# Shield_Grove_I2C.net
KiCad netlist of a schematic drawn in EAGLE
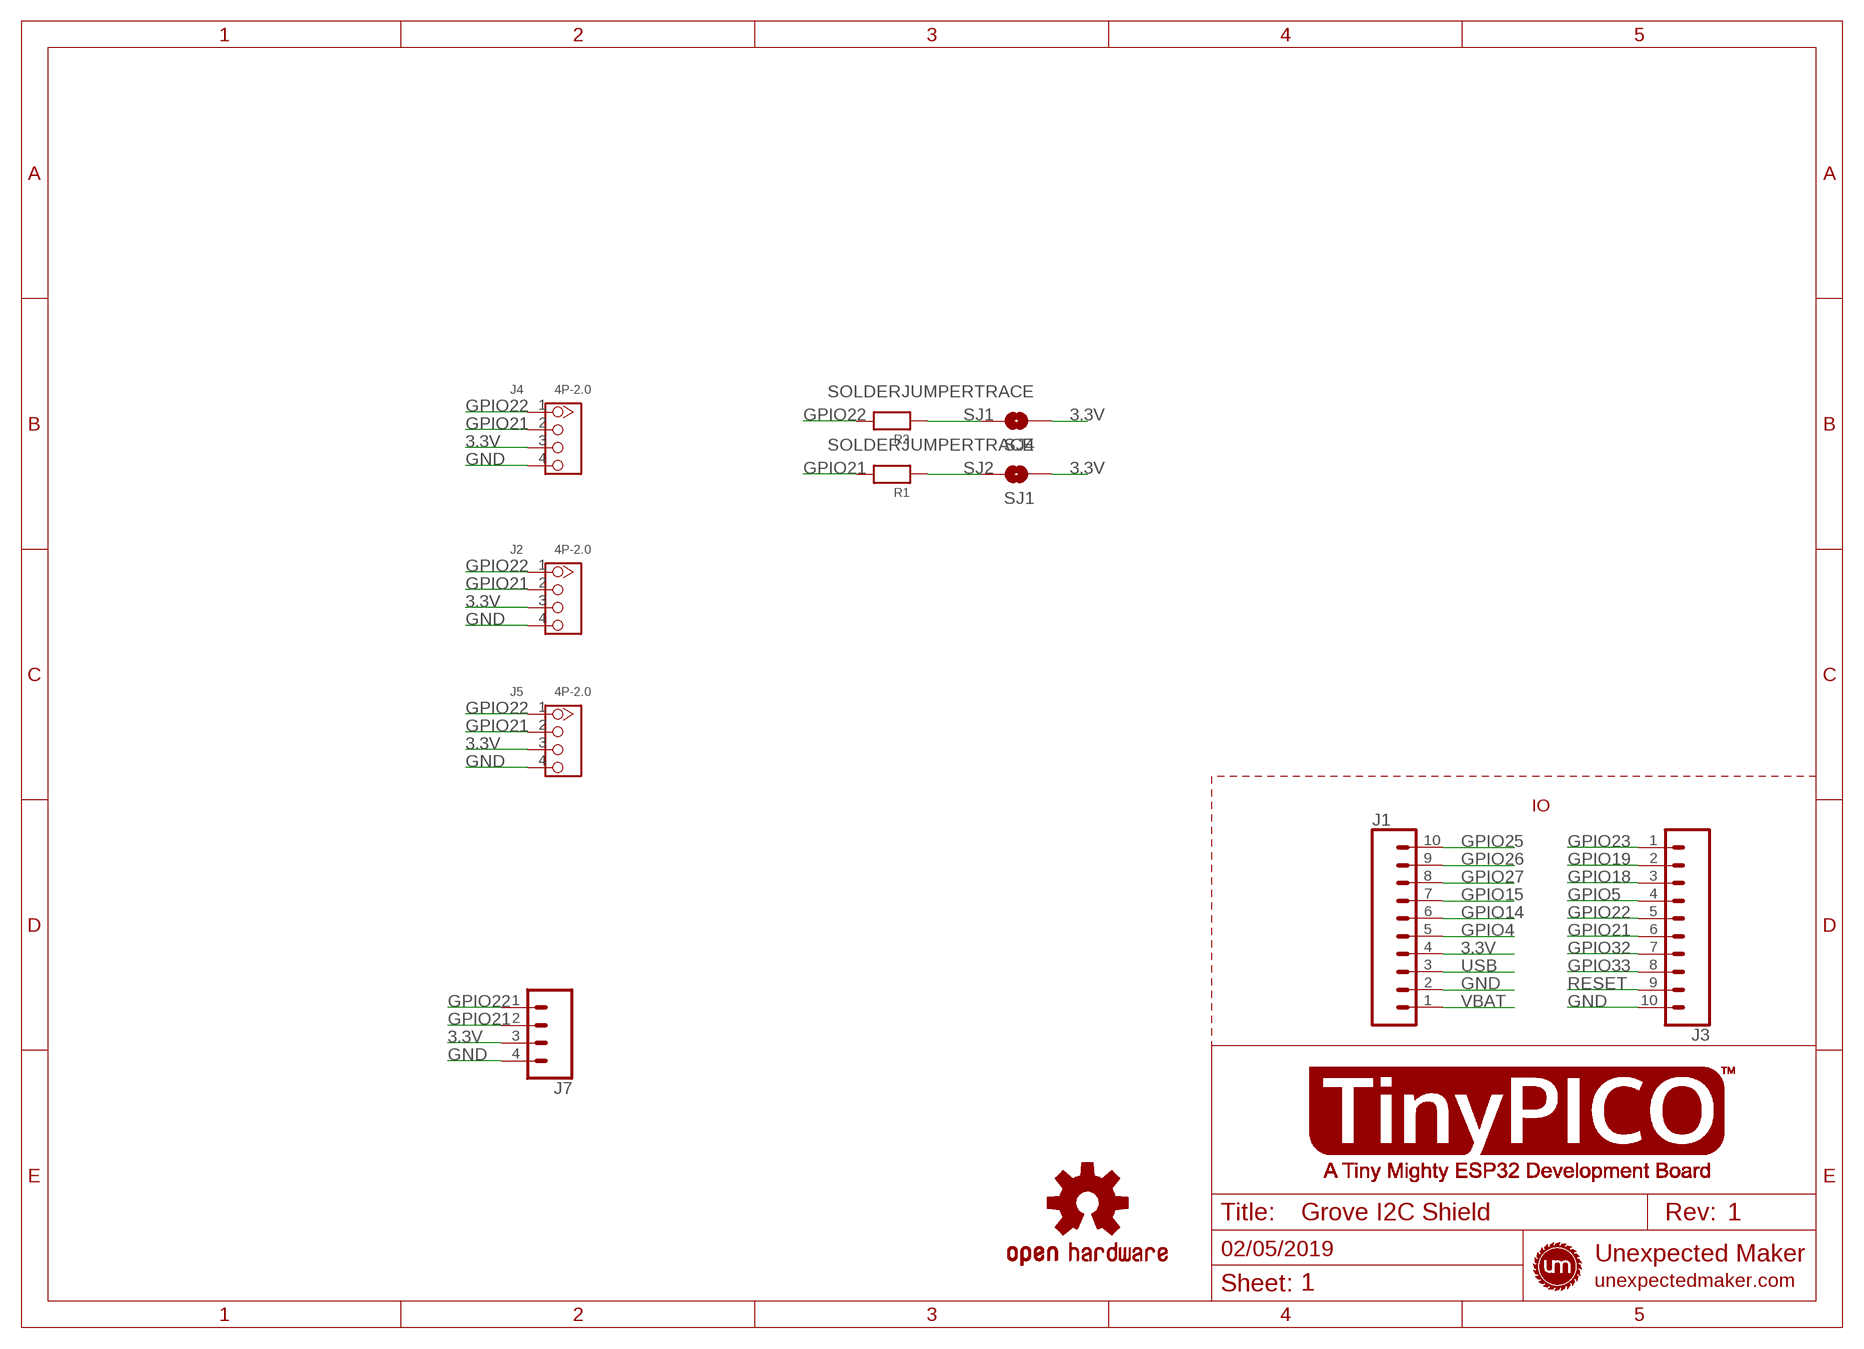
[diagram p0: schematic, sheet 1]

(export (version "E")
  (design (tool "Eeschema 10.0.6"))
  (components
    (comp (ref "J1")
      (value "TINYPICO_HEADER_10NO_SILK_PTH_FEMALE")
      (footprint "eagle-import:1X10_NO_SILK")
      (libsource (lib "eagle-import") (part "TINYPICO_HEADER_10NO_SILK_PTH_FEMALE"))
    )
    (comp (ref "J2")
      (value "4P-2.0")
      (footprint "eagle-import:HW4-2.0")
      (libsource (lib "eagle-import") (part "GROVE-CONNECTOR-DIP(4P-2.0)"))
    )
    (comp (ref "J3")
      (value "TINYPICO_HEADER_10NO_SILK_PTH_FEMALE")
      (footprint "eagle-import:1X10_NO_SILK")
      (libsource (lib "eagle-import") (part "TINYPICO_HEADER_10NO_SILK_PTH_FEMALE"))
    )
    (comp (ref "J4")
      (value "4P-2.0")
      (footprint "eagle-import:HW4-2.0")
      (libsource (lib "eagle-import") (part "GROVE-CONNECTOR-DIP(4P-2.0)"))
    )
    (comp (ref "J5")
      (value "4P-2.0")
      (footprint "eagle-import:HW4-2.0")
      (libsource (lib "eagle-import") (part "GROVE-CONNECTOR-DIP(4P-2.0)"))
    )
    (comp (ref "J7")
      (value "CONN_041X04_NO_SILK")
      (footprint "eagle-import:1X04_NO_SILK")
      (libsource (lib "eagle-import") (part "CONN_041X04_NO_SILK"))
    )
    (comp (ref "LOGO1")
      (value "OSHW-LOGOS")
      (footprint "eagle-import:OSHW-LOGO-S")
      (libsource (lib "eagle-import") (part "OSHW-LOGOS"))
    )
    (comp (ref "R1")
      (value "RESISTOR_0603MP")
      (footprint "eagle-import:_0603MP")
      (libsource (lib "eagle-import") (part "RESISTOR_0603MP"))
    )
    (comp (ref "R2")
      (value "RESISTOR_0603MP")
      (footprint "eagle-import:_0603MP")
      (libsource (lib "eagle-import") (part "RESISTOR_0603MP"))
    )
    (comp (ref "SJ1")
      (value "SOLDERJUMPERTRACE")
      (footprint "eagle-import:SPARKFUN_SJ_2S-TRACE")
      (libsource (lib "eagle-import") (part "SOLDERJUMPERTRACE"))
    )
    (comp (ref "SJ4")
      (value "SOLDERJUMPERTRACE")
      (footprint "eagle-import:SPARKFUN_SJ_2S-TRACE")
      (libsource (lib "eagle-import") (part "SOLDERJUMPERTRACE"))
    )
  )
  (nets
    (net (code "1") (name "/3.3V") (class "Default")
      (node (ref "J1") (pin "4") (pinfunction "4_4") (pintype "passive"))
      (node (ref "J2") (pin "3") (pinfunction "3_3") (pintype "bidirectional"))
      (node (ref "J4") (pin "3") (pinfunction "3_3") (pintype "bidirectional"))
      (node (ref "J5") (pin "3") (pinfunction "3_3") (pintype "bidirectional"))
      (node (ref "J7") (pin "3") (pinfunction "3_3") (pintype "passive"))
      (node (ref "SJ1") (pin "1") (pinfunction "1_1") (pintype "passive"))
      (node (ref "SJ4") (pin "1") (pinfunction "1_1") (pintype "passive"))
    )
    (net (code "2") (name "/GND") (class "Default")
      (node (ref "J1") (pin "2") (pinfunction "2_2") (pintype "passive"))
      (node (ref "J2") (pin "4") (pinfunction "4_4") (pintype "bidirectional"))
      (node (ref "J3") (pin "10") (pinfunction "10_10") (pintype "passive"))
      (node (ref "J4") (pin "4") (pinfunction "4_4") (pintype "bidirectional"))
      (node (ref "J5") (pin "4") (pinfunction "4_4") (pintype "bidirectional"))
      (node (ref "J7") (pin "4") (pinfunction "4_4") (pintype "passive"))
    )
    (net (code "3") (name "/GPIO4") (class "Default")
      (node (ref "J1") (pin "5") (pinfunction "5_5") (pintype "passive"))
    )
    (net (code "4") (name "/GPIO5") (class "Default")
      (node (ref "J3") (pin "4") (pinfunction "4_4") (pintype "passive"))
    )
    (net (code "5") (name "/GPIO14") (class "Default")
      (node (ref "J1") (pin "6") (pinfunction "6_6") (pintype "passive"))
    )
    (net (code "6") (name "/GPIO15") (class "Default")
      (node (ref "J1") (pin "7") (pinfunction "7_7") (pintype "passive"))
    )
    (net (code "7") (name "/GPIO18") (class "Default")
      (node (ref "J3") (pin "3") (pinfunction "3_3") (pintype "passive"))
    )
    (net (code "8") (name "/GPIO19") (class "Default")
      (node (ref "J3") (pin "2") (pinfunction "2_2") (pintype "passive"))
    )
    (net (code "9") (name "/GPIO21") (class "Default")
      (node (ref "J2") (pin "2") (pinfunction "2_2") (pintype "bidirectional"))
      (node (ref "J3") (pin "6") (pinfunction "6_6") (pintype "passive"))
      (node (ref "J4") (pin "2") (pinfunction "2_2") (pintype "bidirectional"))
      (node (ref "J5") (pin "2") (pinfunction "2_2") (pintype "bidirectional"))
      (node (ref "J7") (pin "2") (pinfunction "2_2") (pintype "passive"))
      (node (ref "R1") (pin "2") (pinfunction "2_2") (pintype "passive"))
    )
    (net (code "10") (name "/GPIO22") (class "Default")
      (node (ref "J2") (pin "1") (pinfunction "1_1") (pintype "bidirectional"))
      (node (ref "J3") (pin "5") (pinfunction "5_5") (pintype "passive"))
      (node (ref "J4") (pin "1") (pinfunction "1_1") (pintype "bidirectional"))
      (node (ref "J5") (pin "1") (pinfunction "1_1") (pintype "bidirectional"))
      (node (ref "J7") (pin "1") (pinfunction "1_1") (pintype "passive"))
      (node (ref "R2") (pin "2") (pinfunction "2_2") (pintype "passive"))
    )
    (net (code "11") (name "/GPIO23") (class "Default")
      (node (ref "J3") (pin "1") (pinfunction "1_1") (pintype "passive"))
    )
    (net (code "12") (name "/GPIO25") (class "Default")
      (node (ref "J1") (pin "10") (pinfunction "10_10") (pintype "passive"))
    )
    (net (code "13") (name "/GPIO26") (class "Default")
      (node (ref "J1") (pin "9") (pinfunction "9_9") (pintype "passive"))
    )
    (net (code "14") (name "/GPIO27") (class "Default")
      (node (ref "J1") (pin "8") (pinfunction "8_8") (pintype "passive"))
    )
    (net (code "15") (name "/GPIO32") (class "Default")
      (node (ref "J3") (pin "7") (pinfunction "7_7") (pintype "passive"))
    )
    (net (code "16") (name "/GPIO33") (class "Default")
      (node (ref "J3") (pin "8") (pinfunction "8_8") (pintype "passive"))
    )
    (net (code "17") (name "/RESET") (class "Default")
      (node (ref "J3") (pin "9") (pinfunction "9_9") (pintype "passive"))
    )
    (net (code "18") (name "/SJ1") (class "Default")
      (node (ref "R2") (pin "1") (pinfunction "1_1") (pintype "passive"))
      (node (ref "SJ4") (pin "2") (pinfunction "2_2") (pintype "passive"))
    )
    (net (code "19") (name "/SJ2") (class "Default")
      (node (ref "R1") (pin "1") (pinfunction "1_1") (pintype "passive"))
      (node (ref "SJ1") (pin "2") (pinfunction "2_2") (pintype "passive"))
    )
    (net (code "20") (name "/USB") (class "Default")
      (node (ref "J1") (pin "3") (pinfunction "3_3") (pintype "passive"))
    )
    (net (code "21") (name "/VBAT") (class "Default")
      (node (ref "J1") (pin "1") (pinfunction "1_1") (pintype "passive"))
    )
  )
)
